# 2230506226.net
KiCad netlist of a schematic drawn in EasyEDA Pro
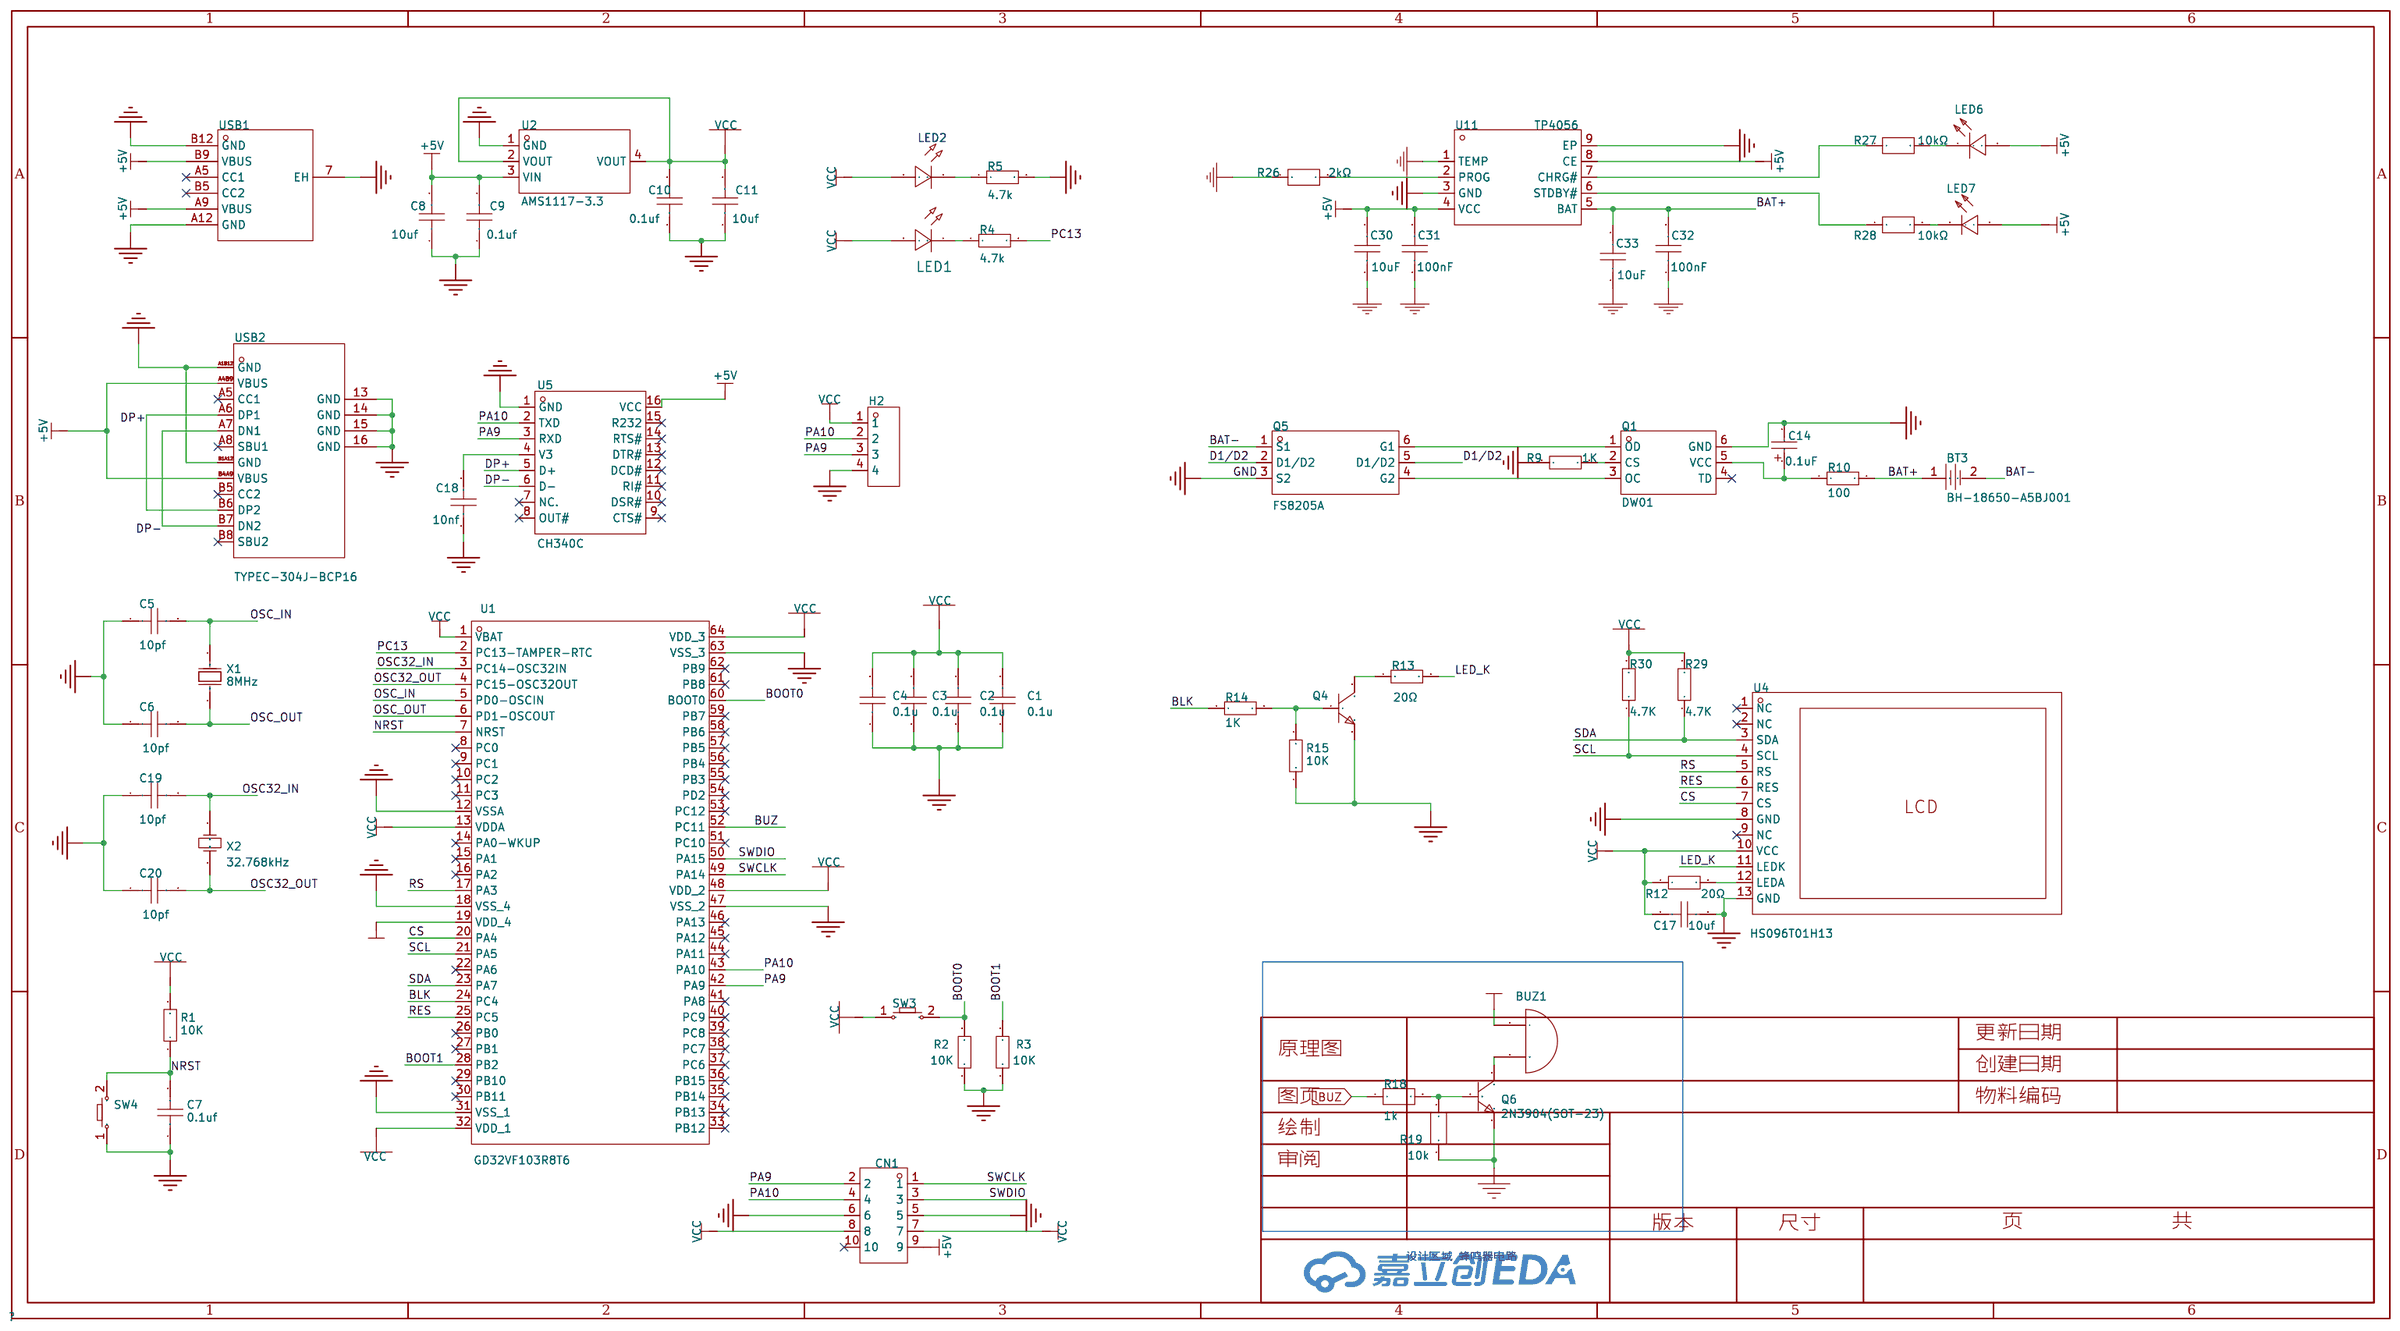
[diagram p0: schematic sheet]

(export (version "E")
  (design (tool "Eeschema 10.0.6"))
  (components
    (comp (ref "BT3")
      (value "BH-18650-A5BJ001")
      (footprint "easyedapro:BAT-TH_18650-A5BJ001")
      (description "BHNi DIP 适用电池18650电芯//电池底座/卧式DIP 电池盒/电池座 材质：PP  镀镍 ，")
      (fields (field (name "Manufacturer") "MYOUNG(美阳)"))
      (libsource (lib "easyedapro") (part "BH-18650-A5BJ001"))
    )
    (comp (ref "BUZ1") (value "BUZ1") (libsource (lib "easyedapro") (part "BUZ1")))
    (comp (ref "C1")
      (value "0.1u")
      (footprint "easyedapro:C0603")
      (libsource (lib "easyedapro") (part "capacitance"))
    )
    (comp (ref "C2")
      (value "0.1u")
      (footprint "easyedapro:C0603")
      (libsource (lib "easyedapro") (part "capacitance"))
    )
    (comp (ref "C3")
      (value "0.1u")
      (footprint "easyedapro:C0603")
      (libsource (lib "easyedapro") (part "capacitance"))
    )
    (comp (ref "C4")
      (value "0.1u")
      (footprint "easyedapro:C0603")
      (libsource (lib "easyedapro") (part "capacitance"))
    )
    (comp (ref "C5")
      (value "10pf")
      (footprint "easyedapro:C0603")
      (libsource (lib "easyedapro") (part "capacitance"))
    )
    (comp (ref "C6")
      (value "10pf")
      (footprint "easyedapro:C0603")
      (libsource (lib "easyedapro") (part "capacitance"))
    )
    (comp (ref "C7")
      (value "0.1uf")
      (footprint "easyedapro:C0603")
      (libsource (lib "easyedapro") (part "capacitance"))
    )
    (comp (ref "C8")
      (value "10uf")
      (footprint "easyedapro:C0603")
      (libsource (lib "easyedapro") (part "capacitance"))
    )
    (comp (ref "C9")
      (value "0.1uf")
      (footprint "easyedapro:C0603")
      (libsource (lib "easyedapro") (part "capacitance"))
    )
    (comp (ref "C10")
      (value "0.1uf")
      (footprint "easyedapro:C0603")
      (libsource (lib "easyedapro") (part "capacitance"))
    )
    (comp (ref "C11")
      (value "10uf")
      (footprint "easyedapro:C0603")
      (libsource (lib "easyedapro") (part "capacitance"))
    )
    (comp (ref "C14")
      (value "0.1uF")
      (footprint "easyedapro:C_Ele_SMD_3x5.4mm")
      (libsource (lib "easyedapro") (part "CAP"))
    )
    (comp (ref "C17")
      (value "10uf")
      (footprint "easyedapro:C0603")
      (libsource (lib "easyedapro") (part "capacitance"))
    )
    (comp (ref "C18")
      (value "10nf")
      (footprint "easyedapro:C0603")
      (libsource (lib "easyedapro") (part "capacitance"))
    )
    (comp (ref "C19")
      (value "10pf")
      (footprint "easyedapro:C0603")
      (libsource (lib "easyedapro") (part "capacitance"))
    )
    (comp (ref "C20")
      (value "10pf")
      (footprint "easyedapro:C0603")
      (libsource (lib "easyedapro") (part "capacitance"))
    )
    (comp (ref "C30")
      (value "10uF")
      (fields (field (name "Manufacturer") "SAMSUNG(三星)"))
      (libsource (lib "easyedapro") (part "10u"))
    )
    (comp (ref "C31")
      (value "100nF")
      (fields (field (name "Manufacturer") "YAGEO(国巨)"))
      (libsource (lib "easyedapro") (part "0.1u"))
    )
    (comp (ref "C32")
      (value "100nF")
      (fields (field (name "Manufacturer") "YAGEO(国巨)"))
      (libsource (lib "easyedapro") (part "0.1u"))
    )
    (comp (ref "C33")
      (value "10uF")
      (fields (field (name "Manufacturer") "SAMSUNG(三星)"))
      (libsource (lib "easyedapro") (part "10u"))
    )
    (comp (ref "CN1") (value "ZX-PZ2.54-2-5PZZ") (libsource (lib "easyedapro") (part "phd-2*5a_c2847737")))
    (comp (ref "H2")
      (value "2.54-1*4P反弯排针")
      (footprint "easyedapro:HDR-TH_4P-P2.54-H-M-W10.4")
      (fields (field (name "Manufacturer") "BOOMELE(博穆精密)"))
      (libsource (lib "easyedapro") (part "2.54-1*4P反弯排针"))
    )
    (comp (ref "LED1")
      (value "~")
      (footprint "easyedapro:LED_0603")
      (libsource (lib "easyedapro") (part "LED_R"))
    )
    (comp (ref "LED2")
      (value "~")
      (footprint "easyedapro:LED_0603")
      (libsource (lib "easyedapro") (part "LED_G"))
    )
    (comp (ref "LED6")
      (value "KT-0603R")
      (fields (field (name "Manufacturer") "KENTO"))
      (libsource (lib "easyedapro") (part "KT-0603R"))
    )
    (comp (ref "LED7") (value "NCD0603B1") (libsource (lib "easyedapro") (part "fc-da1608bk-470h10")))
    (comp (ref "Q1")
      (value "DW01")
      (footprint "easyedapro:SOT-23-6_L2.9-W1.6-P0.95-LS2.8-BR")
      (fields (field (name "Manufacturer") "Hottech(合科泰)"))
      (libsource (lib "easyedapro") (part "DW01"))
    )
    (comp (ref "Q4")
      (value "~")
      (footprint "easyedapro:S8050_SOT-23")
      (libsource (lib "easyedapro") (part "NPN"))
    )
    (comp (ref "Q5")
      (value "FS8205A")
      (footprint "easyedapro:SOT-23-6_L2.9-W1.6-P0.95-LS2.8-BR")
      (fields (field (name "Manufacturer") "TECH PUBLIC(台舟)"))
      (libsource (lib "easyedapro") (part "FS8205A_C2830320"))
    )
    (comp (ref "Q6")
      (value "2N3904(SOT-23)")
      (fields (field (name "Manufacturer Part") "2n3904S-RTK/PS") (field (name "Manufacturer") "KEC"))
      (libsource (lib "easyedapro") (part "2N3904(SOT-23)"))
    )
    (comp (ref "R1") (value "10K") (libsource (lib "easyedapro") (part "电阻")))
    (comp (ref "R2") (value "10K") (libsource (lib "easyedapro") (part "电阻")))
    (comp (ref "R3") (value "10K") (libsource (lib "easyedapro") (part "电阻")))
    (comp (ref "R4") (value "4.7k") (libsource (lib "easyedapro") (part "电阻")))
    (comp (ref "R5") (value "4.7k") (libsource (lib "easyedapro") (part "电阻")))
    (comp (ref "R9") (value "1K") (libsource (lib "easyedapro") (part "电阻")))
    (comp (ref "R10") (value "100") (libsource (lib "easyedapro") (part "电阻")))
    (comp (ref "R12") (value "20Ω") (libsource (lib "easyedapro") (part "电阻")))
    (comp (ref "R13") (value "20Ω") (libsource (lib "easyedapro") (part "电阻")))
    (comp (ref "R14") (value "1K") (libsource (lib "easyedapro") (part "电阻")))
    (comp (ref "R15") (value "10K") (libsource (lib "easyedapro") (part "电阻")))
    (comp (ref "R18") (value "1k") (libsource (lib "easyedapro") (part "1k")))
    (comp (ref "R19") (value "10k") (libsource (lib "easyedapro") (part "10k")))
    (comp (ref "R26")
      (value "2kΩ")
      (fields (field (name "Manufacturer") "UNI-ROYAL(厚声)"))
      (libsource (lib "easyedapro") (part "2k"))
    )
    (comp (ref "R27")
      (value "10kΩ")
      (fields (field (name "Manufacturer") "UNI-ROYAL(厚声)"))
      (libsource (lib "easyedapro") (part "10k"))
    )
    (comp (ref "R28")
      (value "10kΩ")
      (fields (field (name "Manufacturer") "UNI-ROYAL(厚声)"))
      (libsource (lib "easyedapro") (part "10k"))
    )
    (comp (ref "R29")
      (value "4.7K")
      (footprint "easyedapro:R0603")
      (libsource (lib "easyedapro") (part "电阻"))
    )
    (comp (ref "R30")
      (value "4.7K")
      (footprint "easyedapro:R0603")
      (libsource (lib "easyedapro") (part "电阻"))
    )
    (comp (ref "SW3")
      (value "~")
      (footprint "easyedapro:Key_SMD_3x4x2")
      (libsource (lib "easyedapro") (part "轻触按键x2"))
    )
    (comp (ref "SW4")
      (value "~")
      (footprint "easyedapro:Key_SMD_3x4x2")
      (libsource (lib "easyedapro") (part "轻触按键x2"))
    )
    (comp (ref "U1")
      (value "GD32VF103R8T6")
      (footprint "easyedapro:LQFP-64_L10.0-W10.0-P0.50-LS12.0-BL")
      (description "CPU内核:RISC-V;程序存储容量:64KB;RAM总容量:20KB;GPIO端口数量:51;工作电压范围:-;CPU最大主频:108MHz;程序存储器类型:FLASH;")
      (fields (field (name "Manufacturer") "GigaDevice(兆易创新)"))
      (libsource (lib "easyedapro") (part "GD32VF103R8T6"))
    )
    (comp (ref "U2")
      (value "AMS1117-3.3")
      (footprint "easyedapro:SOT-223-3_L6.5-W3.4-P2.30-LS7.0-BR")
      (description "输出类型:固定;最大输入电压:-;输出电压:3.3V;最大输出电流:1A;电源纹波抑制比(PSRR):72dB@(120Hz);输出极性:正极;")
      (fields (field (name "Manufacturer") "AMS"))
      (libsource (lib "easyedapro") (part "AMS1117-3.3"))
    )
    (comp (ref "U4")
      (value "HS096T01H13")
      (footprint "easyedapro:LCD-SMD_HS096T01H13")
      (description "主控芯片:ST7735;尺寸(inch):0.96;")
      (fields (field (name "Manufacturer") "HS(汉昇)"))
      (libsource (lib "easyedapro") (part "HS096T01H13"))
    )
    (comp (ref "U5")
      (value "CH340C")
      (footprint "easyedapro:SOP-16_L10.0-W3.9-P1.27-LS6.0-BL")
      (description "应用功能:收发器;接口协议:USB 2.0;数据速率:2Mbps;")
      (fields (field (name "Manufacturer") "WCH(南京沁恒)"))
      (libsource (lib "easyedapro") (part "CH340C"))
    )
    (comp (ref "U11")
      (value "TP4056")
      (fields (field (name "Manufacturer") "UMW(友台半导体)"))
      (libsource (lib "easyedapro") (part "TP4056_C725790"))
    )
    (comp (ref "USB1")
      (value "TYPE-C 6P")
      (footprint "easyedapro:TYPE-C-SMD_TYPE-C-6P")
      (description "连接器类型:Type-C;标准:-;公母:母;端口数量:1;触点数量:6P;安装方式:卧贴;额定电流 - 电源:-;工作温度范围:-40°C~+85°C;")
      (fields (field (name "Manufacturer") "SHOU HAN(首韩)"))
      (libsource (lib "easyedapro") (part "TYPE-C 6P"))
    )
    (comp (ref "USB2")
      (value "TYPEC-304J-BCP16")
      (footprint "easyedapro:USB-C-SMD_TYPEC-304J-BCP16")
      (fields (field (name "Manufacturer") "XUNPU(讯普)"))
      (libsource (lib "easyedapro") (part "TYPEC-304J-BCP16"))
    )
    (comp (ref "X1")
      (value "8MHz")
      (footprint "easyedapro:CRYSTAL-SMD_L11.5-W4.8-LS12.7")
      (description "晶振类型:贴片晶振;频率:8MHz;常温频差:±20ppm;外接负载电容:20pF;频率稳定度(全温):±30ppm;")
      (fields (field (name "Manufacturer Part") "X49SM8MSD2SC") (field (name "Manufacturer") "YXC(扬兴晶振)"))
      (libsource (lib "easyedapro") (part "X49SM8MSD2SC"))
    )
    (comp (ref "X2")
      (value "32.768kHz")
      (footprint "easyedapro:OSC-TH_BD3.1-P0.8-D0.3")
      (description "晶振类型:直插晶振;频率:32.768kHz;常温频差:±10ppm;外接负载电容:12.5pF;频率稳定度(全温):-;")
      (fields (field (name "Manufacturer Part") "X308032768KGB2SC") (field (name "Manufacturer") "YXC(扬兴晶振)"))
      (libsource (lib "easyedapro") (part "X308032768KGB2SC"))
    )
  )
  (nets
    (net (code "1") (name "+5V") (class "Default")
      (node (ref "C30") (pin "2") (pinfunction "2_2") (pintype "unspecified"))
      (node (ref "C31") (pin "2") (pinfunction "2_2") (pintype "unspecified"))
      (node (ref "C8") (pin "2") (pinfunction "2_2") (pintype "input"))
      (node (ref "C9") (pin "2") (pinfunction "2_2") (pintype "input"))
      (node (ref "CN1") (pin "9") (pinfunction "9_9") (pintype "unspecified"))
      (node (ref "LED6") (pin "2") (pinfunction "A_2") (pintype "unspecified"))
      (node (ref "LED7") (pin "2") (pinfunction "+_2") (pintype "input"))
      (node (ref "U11") (pin "4") (pinfunction "VCC_4") (pintype "unspecified"))
      (node (ref "U11") (pin "8") (pinfunction "CE_8") (pintype "unspecified"))
      (node (ref "U2") (pin "3") (pinfunction "VIN_3") (pintype "unspecified"))
      (node (ref "U5") (pin "16") (pinfunction "VCC_16") (pintype "unspecified"))
      (node (ref "USB1") (pin "A9") (pinfunction "VBUS_A9") (pintype "unspecified"))
      (node (ref "USB1") (pin "B9") (pinfunction "VBUS_B9") (pintype "unspecified"))
      (node (ref "USB2") (pin "A4B9") (pinfunction "VBUS_A4B9") (pintype "unspecified"))
      (node (ref "USB2") (pin "B4A9") (pinfunction "VBUS_B4A9") (pintype "unspecified"))
    )
    (net (code "2") (name "/BAT+") (class "Default")
      (node (ref "BT3") (pin "1") (pinfunction "1_1") (pintype "input"))
      (node (ref "C32") (pin "2") (pinfunction "2_2") (pintype "unspecified"))
      (node (ref "C33") (pin "2") (pinfunction "2_2") (pintype "unspecified"))
      (node (ref "R10") (pin "2") (pinfunction "2_2") (pintype "input"))
      (node (ref "U11") (pin "5") (pinfunction "BAT_5") (pintype "unspecified"))
    )
    (net (code "3") (name "/BAT-") (class "Default")
      (node (ref "BT3") (pin "2") (pinfunction "2_2") (pintype "input"))
      (node (ref "Q5") (pin "1") (pinfunction "S1_1") (pintype "unspecified"))
    )
    (net (code "4") (name "/BLK") (class "Default")
      (node (ref "R14") (pin "1") (pinfunction "1_1") (pintype "input"))
      (node (ref "U1") (pin "24") (pinfunction "PC4_24") (pintype "input"))
    )
    (net (code "5") (name "/BOOT0") (class "Default")
      (node (ref "R2") (pin "2") (pinfunction "2_2") (pintype "input"))
      (node (ref "SW3") (pin "2") (pinfunction "2_2") (pintype "input"))
      (node (ref "U1") (pin "60") (pinfunction "BOOT0_60") (pintype "input"))
    )
    (net (code "6") (name "/BOOT1") (class "Default")
      (node (ref "R3") (pin "2") (pinfunction "2_2") (pintype "input"))
      (node (ref "U1") (pin "28") (pinfunction "PB2_28") (pintype "input"))
    )
    (net (code "7") (name "/CS") (class "Default")
      (node (ref "U1") (pin "20") (pinfunction "PA4_20") (pintype "input"))
      (node (ref "U4") (pin "7") (pinfunction "CS_7") (pintype "unspecified"))
    )
    (net (code "8") (name "/D1{slash}D2") (class "Default")
      (node (ref "Q5") (pin "2") (pinfunction "D1/D2_2") (pintype "unspecified"))
      (node (ref "Q5") (pin "5") (pinfunction "D1/D2_5") (pintype "unspecified"))
    )
    (net (code "9") (name "/DP+") (class "Default")
      (node (ref "U5") (pin "5") (pinfunction "D+_5") (pintype "unspecified"))
      (node (ref "USB2") (pin "A6") (pinfunction "DP1_A6") (pintype "unspecified"))
      (node (ref "USB2") (pin "B6") (pinfunction "DP2_B6") (pintype "unspecified"))
    )
    (net (code "10") (name "/DP-") (class "Default")
      (node (ref "U5") (pin "6") (pinfunction "D-_6") (pintype "unspecified"))
      (node (ref "USB2") (pin "A7") (pinfunction "DN1_A7") (pintype "unspecified"))
      (node (ref "USB2") (pin "B7") (pinfunction "DN2_B7") (pintype "unspecified"))
    )
    (net (code "11") (name "/LED_K") (class "Default")
      (node (ref "R13") (pin "2") (pinfunction "2_2") (pintype "input"))
      (node (ref "U4") (pin "11") (pinfunction "LEDK_11") (pintype "unspecified"))
    )
    (net (code "12") (name "/NRST") (class "Default")
      (node (ref "C7") (pin "2") (pinfunction "2_2") (pintype "input"))
      (node (ref "R1") (pin "1") (pinfunction "1_1") (pintype "input"))
      (node (ref "SW4") (pin "2") (pinfunction "2_2") (pintype "input"))
      (node (ref "U1") (pin "7") (pinfunction "NRST_7") (pintype "input"))
    )
    (net (code "13") (name "/OSC32_IN") (class "Default")
      (node (ref "C19") (pin "2") (pinfunction "2_2") (pintype "input"))
      (node (ref "U1") (pin "3") (pinfunction "PC14-OSC32IN_3") (pintype "input"))
      (node (ref "X2") (pin "1") (pinfunction "OSC1_1") (pintype "unspecified"))
    )
    (net (code "14") (name "/OSC32_OUT") (class "Default")
      (node (ref "C20") (pin "2") (pinfunction "2_2") (pintype "input"))
      (node (ref "U1") (pin "4") (pinfunction "PC15-OSC32OUT_4") (pintype "input"))
      (node (ref "X2") (pin "2") (pinfunction "OSC2_2") (pintype "unspecified"))
    )
    (net (code "15") (name "/OSC_IN") (class "Default")
      (node (ref "C5") (pin "2") (pinfunction "2_2") (pintype "input"))
      (node (ref "U1") (pin "5") (pinfunction "PD0-OSCIN_5") (pintype "input"))
      (node (ref "X1") (pin "1") (pinfunction "OSC1_1") (pintype "input"))
    )
    (net (code "16") (name "/OSC_OUT") (class "Default")
      (node (ref "C6") (pin "2") (pinfunction "2_2") (pintype "input"))
      (node (ref "U1") (pin "6") (pinfunction "PD1-OSCOUT_6") (pintype "input"))
      (node (ref "X1") (pin "2") (pinfunction "OSC2_2") (pintype "input"))
    )
    (net (code "17") (name "/PA9") (class "Default")
      (node (ref "CN1") (pin "2") (pinfunction "2_2") (pintype "unspecified"))
      (node (ref "H2") (pin "3") (pinfunction "3_3") (pintype "unspecified"))
      (node (ref "U1") (pin "42") (pinfunction "PA9_42") (pintype "input"))
      (node (ref "U5") (pin "3") (pinfunction "RXD_3") (pintype "unspecified"))
    )
    (net (code "18") (name "/PA10") (class "Default")
      (node (ref "CN1") (pin "4") (pinfunction "4_4") (pintype "unspecified"))
      (node (ref "H2") (pin "2") (pinfunction "2_2") (pintype "unspecified"))
      (node (ref "U1") (pin "43") (pinfunction "PA10_43") (pintype "input"))
      (node (ref "U5") (pin "2") (pinfunction "TXD_2") (pintype "unspecified"))
    )
    (net (code "19") (name "/PC13") (class "Default")
      (node (ref "R4") (pin "2") (pinfunction "2_2") (pintype "input"))
      (node (ref "U1") (pin "2") (pinfunction "PC13-TAMPER-RTC_2") (pintype "input"))
    )
    (net (code "20") (name "/RES") (class "Default")
      (node (ref "U1") (pin "25") (pinfunction "PC5_25") (pintype "input"))
      (node (ref "U4") (pin "6") (pinfunction "RES_6") (pintype "unspecified"))
    )
    (net (code "21") (name "/RS") (class "Default")
      (node (ref "U1") (pin "17") (pinfunction "PA3_17") (pintype "input"))
      (node (ref "U4") (pin "5") (pinfunction "RS_5") (pintype "unspecified"))
    )
    (net (code "22") (name "/SCL") (class "Default")
      (node (ref "R30") (pin "1") (pinfunction "1_1") (pintype "input"))
      (node (ref "U1") (pin "21") (pinfunction "PA5_21") (pintype "input"))
      (node (ref "U4") (pin "4") (pinfunction "SCL_4") (pintype "unspecified"))
    )
    (net (code "23") (name "/SDA") (class "Default")
      (node (ref "R29") (pin "1") (pinfunction "1_1") (pintype "input"))
      (node (ref "U1") (pin "23") (pinfunction "PA7_23") (pintype "input"))
      (node (ref "U4") (pin "3") (pinfunction "SDA_3") (pintype "unspecified"))
    )
    (net (code "24") (name "/SWCLK") (class "Default")
      (node (ref "CN1") (pin "1") (pinfunction "1_1") (pintype "unspecified"))
      (node (ref "U1") (pin "49") (pinfunction "PA14_49") (pintype "input"))
    )
    (net (code "25") (name "/SWDIO") (class "Default")
      (node (ref "CN1") (pin "3") (pinfunction "3_3") (pintype "unspecified"))
      (node (ref "U1") (pin "50") (pinfunction "PA15_50") (pintype "input"))
    )
    (net (code "26") (name "BUZ") (class "Default")
      (node (ref "R18") (pin "1") (pinfunction "1_1") (pintype "input"))
      (node (ref "U1") (pin "52") (pinfunction "PC11_52") (pintype "input"))
    )
    (net (code "27") (name "GND") (class "Default")
      (node (ref "C1") (pin "1") (pinfunction "1_1") (pintype "input"))
      (node (ref "C10") (pin "1") (pinfunction "1_1") (pintype "input"))
      (node (ref "C11") (pin "1") (pinfunction "1_1") (pintype "input"))
      (node (ref "C14") (pin "2") (pinfunction "2_2") (pintype "input"))
      (node (ref "C17") (pin "2") (pinfunction "2_2") (pintype "input"))
      (node (ref "C18") (pin "1") (pinfunction "1_1") (pintype "input"))
      (node (ref "C19") (pin "1") (pinfunction "1_1") (pintype "input"))
      (node (ref "C2") (pin "1") (pinfunction "1_1") (pintype "input"))
      (node (ref "C20") (pin "1") (pinfunction "1_1") (pintype "input"))
      (node (ref "C3") (pin "1") (pinfunction "1_1") (pintype "input"))
      (node (ref "C30") (pin "1") (pinfunction "1_1") (pintype "unspecified"))
      (node (ref "C31") (pin "1") (pinfunction "1_1") (pintype "unspecified"))
      (node (ref "C32") (pin "1") (pinfunction "1_1") (pintype "unspecified"))
      (node (ref "C33") (pin "1") (pinfunction "1_1") (pintype "unspecified"))
      (node (ref "C4") (pin "1") (pinfunction "1_1") (pintype "input"))
      (node (ref "C5") (pin "1") (pinfunction "1_1") (pintype "input"))
      (node (ref "C6") (pin "1") (pinfunction "1_1") (pintype "input"))
      (node (ref "C7") (pin "1") (pinfunction "1_1") (pintype "input"))
      (node (ref "C8") (pin "1") (pinfunction "1_1") (pintype "input"))
      (node (ref "C9") (pin "1") (pinfunction "1_1") (pintype "input"))
      (node (ref "CN1") (pin "5") (pinfunction "5_5") (pintype "unspecified"))
      (node (ref "CN1") (pin "6") (pinfunction "6_6") (pintype "unspecified"))
      (node (ref "H2") (pin "4") (pinfunction "4_4") (pintype "unspecified"))
      (node (ref "Q1") (pin "6") (pinfunction "GND_6") (pintype "input"))
      (node (ref "Q4") (pin "2") (pinfunction "2_2") (pintype "unspecified"))
      (node (ref "Q5") (pin "3") (pinfunction "S2_3") (pintype "unspecified"))
      (node (ref "Q6") (pin "1") (pinfunction "E_1") (pintype "input"))
      (node (ref "R15") (pin "1") (pinfunction "1_1") (pintype "input"))
      (node (ref "R19") (pin "2") (pinfunction "2_2") (pintype "unspecified"))
      (node (ref "R2") (pin "1") (pinfunction "1_1") (pintype "input"))
      (node (ref "R26") (pin "1") (pinfunction "1_1") (pintype "unspecified"))
      (node (ref "R3") (pin "1") (pinfunction "1_1") (pintype "input"))
      (node (ref "R5") (pin "2") (pinfunction "2_2") (pintype "input"))
      (node (ref "R9") (pin "1") (pinfunction "1_1") (pintype "input"))
      (node (ref "SW4") (pin "1") (pinfunction "1_1") (pintype "input"))
      (node (ref "U1") (pin "12") (pinfunction "VSSA_12") (pintype "input"))
      (node (ref "U1") (pin "18") (pinfunction "VSS_4_18") (pintype "input"))
      (node (ref "U1") (pin "31") (pinfunction "VSS_1_31") (pintype "input"))
      (node (ref "U1") (pin "47") (pinfunction "VSS_2_47") (pintype "input"))
      (node (ref "U1") (pin "63") (pinfunction "VSS_3_63") (pintype "input"))
      (node (ref "U11") (pin "1") (pinfunction "TEMP_1") (pintype "unspecified"))
      (node (ref "U11") (pin "3") (pinfunction "GND_3") (pintype "unspecified"))
      (node (ref "U11") (pin "9") (pinfunction "EP_9") (pintype "unspecified"))
      (node (ref "U2") (pin "1") (pinfunction "GND_1") (pintype "unspecified"))
      (node (ref "U4") (pin "13") (pinfunction "GND_13") (pintype "unspecified"))
      (node (ref "U4") (pin "8") (pinfunction "GND_8") (pintype "unspecified"))
      (node (ref "U5") (pin "1") (pinfunction "GND_1") (pintype "unspecified"))
      (node (ref "USB1") (pin "7") (pinfunction "EH_7") (pintype "unspecified"))
      (node (ref "USB1") (pin "A12") (pinfunction "GND_A12") (pintype "unspecified"))
      (node (ref "USB1") (pin "B12") (pinfunction "GND_B12") (pintype "unspecified"))
      (node (ref "USB2") (pin "13") (pinfunction "GND_13") (pintype "unspecified"))
      (node (ref "USB2") (pin "14") (pinfunction "GND_14") (pintype "unspecified"))
      (node (ref "USB2") (pin "15") (pinfunction "GND_15") (pintype "unspecified"))
      (node (ref "USB2") (pin "16") (pinfunction "GND_16") (pintype "unspecified"))
      (node (ref "USB2") (pin "A1B12") (pinfunction "GND_A1B12") (pintype "unspecified"))
      (node (ref "USB2") (pin "B1A12") (pinfunction "GND_B1A12") (pintype "unspecified"))
    )
    (net (code "28") (name "Net-(BUZ1-B)") (class "Default")
      (node (ref "BUZ1") (pin "2") (pinfunction "B_2") (pintype "input"))
      (node (ref "Q6") (pin "3") (pinfunction "C_3") (pintype "input"))
    )
    (net (code "29") (name "Net-(LED1-C)") (class "Default")
      (node (ref "LED1") (pin "1") (pinfunction "C_1") (pintype "input"))
      (node (ref "R4") (pin "1") (pinfunction "1_1") (pintype "input"))
    )
    (net (code "30") (name "Net-(LED2-C)") (class "Default")
      (node (ref "LED2") (pin "1") (pinfunction "C_1") (pintype "input"))
      (node (ref "R5") (pin "1") (pinfunction "1_1") (pintype "input"))
    )
    (net (code "31") (name "Net-(LED6-K)") (class "Default")
      (node (ref "LED6") (pin "1") (pinfunction "K_1") (pintype "unspecified"))
      (node (ref "R27") (pin "2") (pinfunction "2_2") (pintype "unspecified"))
    )
    (net (code "32") (name "Net-(LED7--)") (class "Default")
      (node (ref "LED7") (pin "1") (pinfunction "-_1") (pintype "input"))
      (node (ref "R28") (pin "2") (pinfunction "2_2") (pintype "unspecified"))
    )
    (net (code "33") (name "Net-(Q1-CS)") (class "Default")
      (node (ref "Q1") (pin "2") (pinfunction "CS_2") (pintype "input"))
      (node (ref "R9") (pin "2") (pinfunction "2_2") (pintype "input"))
    )
    (net (code "34") (name "Net-(Q1-OC)") (class "Default")
      (node (ref "Q1") (pin "3") (pinfunction "OC_3") (pintype "input"))
      (node (ref "Q5") (pin "4") (pinfunction "G2_4") (pintype "unspecified"))
    )
    (net (code "35") (name "Net-(Q1-OD)") (class "Default")
      (node (ref "Q1") (pin "1") (pinfunction "OD_1") (pintype "input"))
      (node (ref "Q5") (pin "6") (pinfunction "G1_6") (pintype "unspecified"))
    )
    (net (code "36") (name "Net-(Q1-VCC)") (class "Default")
      (node (ref "C14") (pin "1") (pinfunction "1_1") (pintype "input"))
      (node (ref "Q1") (pin "5") (pinfunction "VCC_5") (pintype "input"))
      (node (ref "R10") (pin "1") (pinfunction "1_1") (pintype "input"))
    )
    (net (code "37") (name "Net-(Q4-Pad1)") (class "Default")
      (node (ref "Q4") (pin "1") (pinfunction "1_1") (pintype "unspecified"))
      (node (ref "R14") (pin "2") (pinfunction "2_2") (pintype "input"))
      (node (ref "R15") (pin "2") (pinfunction "2_2") (pintype "input"))
    )
    (net (code "38") (name "Net-(Q4-Pad3)") (class "Default")
      (node (ref "Q4") (pin "3") (pinfunction "3_3") (pintype "unspecified"))
      (node (ref "R13") (pin "1") (pinfunction "1_1") (pintype "input"))
    )
    (net (code "39") (name "Net-(Q6-B)") (class "Default")
      (node (ref "Q6") (pin "2") (pinfunction "B_2") (pintype "input"))
      (node (ref "R18") (pin "2") (pinfunction "2_2") (pintype "input"))
      (node (ref "R19") (pin "1") (pinfunction "1_1") (pintype "unspecified"))
    )
    (net (code "40") (name "Net-(U4-LEDA)") (class "Default")
      (node (ref "R12") (pin "2") (pinfunction "2_2") (pintype "input"))
      (node (ref "U4") (pin "12") (pinfunction "LEDA_12") (pintype "unspecified"))
    )
    (net (code "41") (name "Net-(U5-V3)") (class "Default")
      (node (ref "C18") (pin "2") (pinfunction "2_2") (pintype "input"))
      (node (ref "U5") (pin "4") (pinfunction "V3_4") (pintype "unspecified"))
    )
    (net (code "42") (name "Net-(U11-CHRG#)") (class "Default")
      (node (ref "R27") (pin "1") (pinfunction "1_1") (pintype "unspecified"))
      (node (ref "U11") (pin "7") (pinfunction "CHRG#_7") (pintype "unspecified"))
    )
    (net (code "43") (name "Net-(U11-PROG)") (class "Default")
      (node (ref "R26") (pin "2") (pinfunction "2_2") (pintype "unspecified"))
      (node (ref "U11") (pin "2") (pinfunction "PROG_2") (pintype "unspecified"))
    )
    (net (code "44") (name "Net-(U11-STDBY#)") (class "Default")
      (node (ref "R28") (pin "1") (pinfunction "1_1") (pintype "unspecified"))
      (node (ref "U11") (pin "6") (pinfunction "STDBY#_6") (pintype "unspecified"))
    )
    (net (code "45") (name "VCC") (class "Default")
      (node (ref "BUZ1") (pin "1") (pinfunction "A_1") (pintype "input"))
      (node (ref "C1") (pin "2") (pinfunction "2_2") (pintype "input"))
      (node (ref "C10") (pin "2") (pinfunction "2_2") (pintype "input"))
      (node (ref "C11") (pin "2") (pinfunction "2_2") (pintype "input"))
      (node (ref "C17") (pin "1") (pinfunction "1_1") (pintype "input"))
      (node (ref "C2") (pin "2") (pinfunction "2_2") (pintype "input"))
      (node (ref "C3") (pin "2") (pinfunction "2_2") (pintype "input"))
      (node (ref "C4") (pin "2") (pinfunction "2_2") (pintype "input"))
      (node (ref "CN1") (pin "7") (pinfunction "7_7") (pintype "unspecified"))
      (node (ref "CN1") (pin "8") (pinfunction "8_8") (pintype "unspecified"))
      (node (ref "H2") (pin "1") (pinfunction "1_1") (pintype "unspecified"))
      (node (ref "LED1") (pin "2") (pinfunction "A_2") (pintype "input"))
      (node (ref "LED2") (pin "2") (pinfunction "A_2") (pintype "input"))
      (node (ref "R1") (pin "2") (pinfunction "2_2") (pintype "input"))
      (node (ref "R12") (pin "1") (pinfunction "1_1") (pintype "input"))
      (node (ref "R29") (pin "2") (pinfunction "2_2") (pintype "input"))
      (node (ref "R30") (pin "2") (pinfunction "2_2") (pintype "input"))
      (node (ref "SW3") (pin "1") (pinfunction "1_1") (pintype "input"))
      (node (ref "U1") (pin "1") (pinfunction "VBAT_1") (pintype "input"))
      (node (ref "U1") (pin "13") (pinfunction "VDDA_13") (pintype "input"))
      (node (ref "U1") (pin "19") (pinfunction "VDD_4_19") (pintype "input"))
      (node (ref "U1") (pin "32") (pinfunction "VDD_1_32") (pintype "input"))
      (node (ref "U1") (pin "48") (pinfunction "VDD_2_48") (pintype "input"))
      (node (ref "U1") (pin "64") (pinfunction "VDD_3_64") (pintype "input"))
      (node (ref "U2") (pin "2") (pinfunction "VOUT_2") (pintype "unspecified"))
      (node (ref "U2") (pin "4") (pinfunction "VOUT_4") (pintype "unspecified"))
      (node (ref "U4") (pin "10") (pinfunction "VCC_10") (pintype "unspecified"))
    )
    (net (code "46") (name "unconnected-(CN1-Pad10)") (class "Default")
      (node (ref "CN1") (pin "10") (pinfunction "10_10") (pintype "unspecified+no_connect"))
    )
    (net (code "47") (name "unconnected-(Q1-TD-Pad4)") (class "Default")
      (node (ref "Q1") (pin "4") (pinfunction "TD_4") (pintype "input+no_connect"))
    )
    (net (code "48") (name "unconnected-(U1-PA0-WKUP-Pad14)") (class "Default")
      (node (ref "U1") (pin "14") (pinfunction "PA0-WKUP_14") (pintype "input+no_connect"))
    )
    (net (code "49") (name "unconnected-(U1-PA1-Pad15)") (class "Default")
      (node (ref "U1") (pin "15") (pinfunction "PA1_15") (pintype "input+no_connect"))
    )
    (net (code "50") (name "unconnected-(U1-PA2-Pad16)") (class "Default")
      (node (ref "U1") (pin "16") (pinfunction "PA2_16") (pintype "input+no_connect"))
    )
    (net (code "51") (name "unconnected-(U1-PA6-Pad22)") (class "Default")
      (node (ref "U1") (pin "22") (pinfunction "PA6_22") (pintype "input+no_connect"))
    )
    (net (code "52") (name "unconnected-(U1-PA8-Pad41)") (class "Default")
      (node (ref "U1") (pin "41") (pinfunction "PA8_41") (pintype "input+no_connect"))
    )
    (net (code "53") (name "unconnected-(U1-PA11-Pad44)") (class "Default")
      (node (ref "U1") (pin "44") (pinfunction "PA11_44") (pintype "input+no_connect"))
    )
    (net (code "54") (name "unconnected-(U1-PA12-Pad45)") (class "Default")
      (node (ref "U1") (pin "45") (pinfunction "PA12_45") (pintype "input+no_connect"))
    )
    (net (code "55") (name "unconnected-(U1-PA13-Pad46)") (class "Default")
      (node (ref "U1") (pin "46") (pinfunction "PA13_46") (pintype "input+no_connect"))
    )
    (net (code "56") (name "unconnected-(U1-PB0-Pad26)") (class "Default")
      (node (ref "U1") (pin "26") (pinfunction "PB0_26") (pintype "input+no_connect"))
    )
    (net (code "57") (name "unconnected-(U1-PB1-Pad27)") (class "Default")
      (node (ref "U1") (pin "27") (pinfunction "PB1_27") (pintype "input+no_connect"))
    )
    (net (code "58") (name "unconnected-(U1-PB3-Pad55)") (class "Default")
      (node (ref "U1") (pin "55") (pinfunction "PB3_55") (pintype "input+no_connect"))
    )
    (net (code "59") (name "unconnected-(U1-PB4-Pad56)") (class "Default")
      (node (ref "U1") (pin "56") (pinfunction "PB4_56") (pintype "input+no_connect"))
    )
    (net (code "60") (name "unconnected-(U1-PB5-Pad57)") (class "Default")
      (node (ref "U1") (pin "57") (pinfunction "PB5_57") (pintype "input+no_connect"))
    )
    (net (code "61") (name "unconnected-(U1-PB6-Pad58)") (class "Default")
      (node (ref "U1") (pin "58") (pinfunction "PB6_58") (pintype "input+no_connect"))
    )
    (net (code "62") (name "unconnected-(U1-PB7-Pad59)") (class "Default")
      (node (ref "U1") (pin "59") (pinfunction "PB7_59") (pintype "input+no_connect"))
    )
    (net (code "63") (name "unconnected-(U1-PB8-Pad61)") (class "Default")
      (node (ref "U1") (pin "61") (pinfunction "PB8_61") (pintype "input+no_connect"))
    )
    (net (code "64") (name "unconnected-(U1-PB9-Pad62)") (class "Default")
      (node (ref "U1") (pin "62") (pinfunction "PB9_62") (pintype "input+no_connect"))
    )
    (net (code "65") (name "unconnected-(U1-PB10-Pad29)") (class "Default")
      (node (ref "U1") (pin "29") (pinfunction "PB10_29") (pintype "input+no_connect"))
    )
    (net (code "66") (name "unconnected-(U1-PB11-Pad30)") (class "Default")
      (node (ref "U1") (pin "30") (pinfunction "PB11_30") (pintype "input+no_connect"))
    )
    (net (code "67") (name "unconnected-(U1-PB12-Pad33)") (class "Default")
      (node (ref "U1") (pin "33") (pinfunction "PB12_33") (pintype "input+no_connect"))
    )
    (net (code "68") (name "unconnected-(U1-PB13-Pad34)") (class "Default")
      (node (ref "U1") (pin "34") (pinfunction "PB13_34") (pintype "input+no_connect"))
    )
    (net (code "69") (name "unconnected-(U1-PB14-Pad35)") (class "Default")
      (node (ref "U1") (pin "35") (pinfunction "PB14_35") (pintype "input+no_connect"))
    )
    (net (code "70") (name "unconnected-(U1-PB15-Pad36)") (class "Default")
      (node (ref "U1") (pin "36") (pinfunction "PB15_36") (pintype "input+no_connect"))
    )
    (net (code "71") (name "unconnected-(U1-PC0-Pad8)") (class "Default")
      (node (ref "U1") (pin "8") (pinfunction "PC0_8") (pintype "input+no_connect"))
    )
    (net (code "72") (name "unconnected-(U1-PC1-Pad9)") (class "Default")
      (node (ref "U1") (pin "9") (pinfunction "PC1_9") (pintype "input+no_connect"))
    )
    (net (code "73") (name "unconnected-(U1-PC2-Pad10)") (class "Default")
      (node (ref "U1") (pin "10") (pinfunction "PC2_10") (pintype "input+no_connect"))
    )
    (net (code "74") (name "unconnected-(U1-PC3-Pad11)") (class "Default")
      (node (ref "U1") (pin "11") (pinfunction "PC3_11") (pintype "input+no_connect"))
    )
    (net (code "75") (name "unconnected-(U1-PC6-Pad37)") (class "Default")
      (node (ref "U1") (pin "37") (pinfunction "PC6_37") (pintype "input+no_connect"))
    )
    (net (code "76") (name "unconnected-(U1-PC7-Pad38)") (class "Default")
      (node (ref "U1") (pin "38") (pinfunction "PC7_38") (pintype "input+no_connect"))
    )
    (net (code "77") (name "unconnected-(U1-PC8-Pad39)") (class "Default")
      (node (ref "U1") (pin "39") (pinfunction "PC8_39") (pintype "input+no_connect"))
    )
    (net (code "78") (name "unconnected-(U1-PC9-Pad40)") (class "Default")
      (node (ref "U1") (pin "40") (pinfunction "PC9_40") (pintype "input+no_connect"))
    )
    (net (code "79") (name "unconnected-(U1-PC10-Pad51)") (class "Default")
      (node (ref "U1") (pin "51") (pinfunction "PC10_51") (pintype "input+no_connect"))
    )
    (net (code "80") (name "unconnected-(U1-PC12-Pad53)") (class "Default")
      (node (ref "U1") (pin "53") (pinfunction "PC12_53") (pintype "input+no_connect"))
    )
    (net (code "81") (name "unconnected-(U1-PD2-Pad54)") (class "Default")
      (node (ref "U1") (pin "54") (pinfunction "PD2_54") (pintype "input+no_connect"))
    )
    (net (code "82") (name "unconnected-(U4-NC-Pad1)") (class "Default")
      (node (ref "U4") (pin "1") (pinfunction "NC_1") (pintype "unspecified+no_connect"))
    )
    (net (code "83") (name "unconnected-(U4-NC-Pad2)") (class "Default")
      (node (ref "U4") (pin "2") (pinfunction "NC_2") (pintype "unspecified+no_connect"))
    )
    (net (code "84") (name "unconnected-(U4-NC-Pad9)") (class "Default")
      (node (ref "U4") (pin "9") (pinfunction "NC_9") (pintype "unspecified+no_connect"))
    )
    (net (code "85") (name "unconnected-(U5-CTS#-Pad9)") (class "Default")
      (node (ref "U5") (pin "9") (pinfunction "CTS#_9") (pintype "unspecified+no_connect"))
    )
    (net (code "86") (name "unconnected-(U5-DCD#-Pad12)") (class "Default")
      (node (ref "U5") (pin "12") (pinfunction "DCD#_12") (pintype "unspecified+no_connect"))
    )
    (net (code "87") (name "unconnected-(U5-DSR#-Pad10)") (class "Default")
      (node (ref "U5") (pin "10") (pinfunction "DSR#_10") (pintype "unspecified+no_connect"))
    )
    (net (code "88") (name "unconnected-(U5-DTR#-Pad13)") (class "Default")
      (node (ref "U5") (pin "13") (pinfunction "DTR#_13") (pintype "unspecified+no_connect"))
    )
    (net (code "89") (name "unconnected-(U5-NC.-Pad7)") (class "Default")
      (node (ref "U5") (pin "7") (pinfunction "NC._7") (pintype "unspecified+no_connect"))
    )
    (net (code "90") (name "unconnected-(U5-OUT#-Pad8)") (class "Default")
      (node (ref "U5") (pin "8") (pinfunction "OUT#_8") (pintype "unspecified+no_connect"))
    )
    (net (code "91") (name "unconnected-(U5-R232-Pad15)") (class "Default")
      (node (ref "U5") (pin "15") (pinfunction "R232_15") (pintype "unspecified+no_connect"))
    )
    (net (code "92") (name "unconnected-(U5-RI#-Pad11)") (class "Default")
      (node (ref "U5") (pin "11") (pinfunction "RI#_11") (pintype "unspecified+no_connect"))
    )
    (net (code "93") (name "unconnected-(U5-RTS#-Pad14)") (class "Default")
      (node (ref "U5") (pin "14") (pinfunction "RTS#_14") (pintype "unspecified+no_connect"))
    )
    (net (code "94") (name "unconnected-(USB1-CC1-PadA5)") (class "Default")
      (node (ref "USB1") (pin "A5") (pinfunction "CC1_A5") (pintype "unspecified+no_connect"))
    )
    (net (code "95") (name "unconnected-(USB1-CC2-PadB5)") (class "Default")
      (node (ref "USB1") (pin "B5") (pinfunction "CC2_B5") (pintype "unspecified+no_connect"))
    )
    (net (code "96") (name "unconnected-(USB2-CC1-PadA5)") (class "Default")
      (node (ref "USB2") (pin "A5") (pinfunction "CC1_A5") (pintype "unspecified+no_connect"))
    )
    (net (code "97") (name "unconnected-(USB2-CC2-PadB5)") (class "Default")
      (node (ref "USB2") (pin "B5") (pinfunction "CC2_B5") (pintype "unspecified+no_connect"))
    )
    (net (code "98") (name "unconnected-(USB2-SBU1-PadA8)") (class "Default")
      (node (ref "USB2") (pin "A8") (pinfunction "SBU1_A8") (pintype "unspecified+no_connect"))
    )
    (net (code "99") (name "unconnected-(USB2-SBU2-PadB8)") (class "Default")
      (node (ref "USB2") (pin "B8") (pinfunction "SBU2_B8") (pintype "unspecified+no_connect"))
    )
  )
)
